# pressure_regulator_8ch.net
KiCad netlist of a schematic drawn in EAGLE
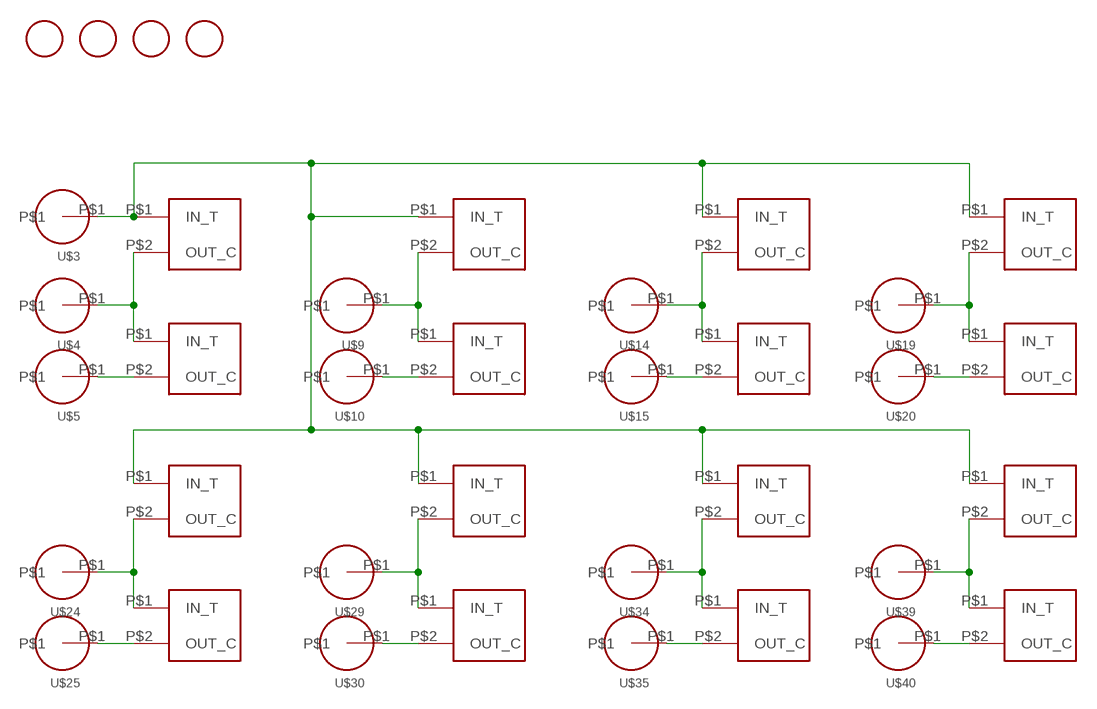
[diagram p0: schematic, sheet 1]

(export (version "E")
  (design (tool "Eeschema 10.0.6"))
  (components
    (comp (ref "U$1")
      (value "PARKER_PROP_VALVE")
      (footprint "eagle-import:PARKER_PROP_VALVE")
      (libsource (lib "eagle-import") (part "PARKER_PROP_VALVE"))
    )
    (comp (ref "U$2")
      (value "PARKER_PROP_VALVE")
      (footprint "eagle-import:PARKER_PROP_VALVE")
      (libsource (lib "eagle-import") (part "PARKER_PROP_VALVE"))
    )
    (comp (ref "U$3")
      (value "10-32_BARBED_CONNECTOR")
      (footprint "eagle-import:10-32_BARBED_CONNECTOR")
      (libsource (lib "eagle-import") (part "10-32_BARBED_CONNECTOR"))
    )
    (comp (ref "U$4")
      (value "10-32_BARBED_CONNECTOR")
      (footprint "eagle-import:10-32_BARBED_CONNECTOR")
      (libsource (lib "eagle-import") (part "10-32_BARBED_CONNECTOR"))
    )
    (comp (ref "U$5")
      (value "10-32_BARBED_CONNECTOR")
      (footprint "eagle-import:10-32_BARBED_CONNECTOR")
      (libsource (lib "eagle-import") (part "10-32_BARBED_CONNECTOR"))
    )
    (comp (ref "U$6")
      (value "PARKER_PROP_VALVE")
      (footprint "eagle-import:PARKER_PROP_VALVE")
      (libsource (lib "eagle-import") (part "PARKER_PROP_VALVE"))
    )
    (comp (ref "U$7")
      (value "PARKER_PROP_VALVE")
      (footprint "eagle-import:PARKER_PROP_VALVE")
      (libsource (lib "eagle-import") (part "PARKER_PROP_VALVE"))
    )
    (comp (ref "U$9")
      (value "10-32_BARBED_CONNECTOR")
      (footprint "eagle-import:10-32_BARBED_CONNECTOR")
      (libsource (lib "eagle-import") (part "10-32_BARBED_CONNECTOR"))
    )
    (comp (ref "U$10")
      (value "10-32_BARBED_CONNECTOR")
      (footprint "eagle-import:10-32_BARBED_CONNECTOR")
      (libsource (lib "eagle-import") (part "10-32_BARBED_CONNECTOR"))
    )
    (comp (ref "U$11")
      (value "PARKER_PROP_VALVE")
      (footprint "eagle-import:PARKER_PROP_VALVE")
      (libsource (lib "eagle-import") (part "PARKER_PROP_VALVE"))
    )
    (comp (ref "U$12")
      (value "PARKER_PROP_VALVE")
      (footprint "eagle-import:PARKER_PROP_VALVE")
      (libsource (lib "eagle-import") (part "PARKER_PROP_VALVE"))
    )
    (comp (ref "U$14")
      (value "10-32_BARBED_CONNECTOR")
      (footprint "eagle-import:10-32_BARBED_CONNECTOR")
      (libsource (lib "eagle-import") (part "10-32_BARBED_CONNECTOR"))
    )
    (comp (ref "U$15")
      (value "10-32_BARBED_CONNECTOR")
      (footprint "eagle-import:10-32_BARBED_CONNECTOR")
      (libsource (lib "eagle-import") (part "10-32_BARBED_CONNECTOR"))
    )
    (comp (ref "U$16")
      (value "PARKER_PROP_VALVE")
      (footprint "eagle-import:PARKER_PROP_VALVE")
      (libsource (lib "eagle-import") (part "PARKER_PROP_VALVE"))
    )
    (comp (ref "U$17")
      (value "PARKER_PROP_VALVE")
      (footprint "eagle-import:PARKER_PROP_VALVE")
      (libsource (lib "eagle-import") (part "PARKER_PROP_VALVE"))
    )
    (comp (ref "U$19")
      (value "10-32_BARBED_CONNECTOR")
      (footprint "eagle-import:10-32_BARBED_CONNECTOR")
      (libsource (lib "eagle-import") (part "10-32_BARBED_CONNECTOR"))
    )
    (comp (ref "U$20")
      (value "10-32_BARBED_CONNECTOR")
      (footprint "eagle-import:10-32_BARBED_CONNECTOR")
      (libsource (lib "eagle-import") (part "10-32_BARBED_CONNECTOR"))
    )
    (comp (ref "U$21")
      (value "PARKER_PROP_VALVE")
      (footprint "eagle-import:PARKER_PROP_VALVE")
      (libsource (lib "eagle-import") (part "PARKER_PROP_VALVE"))
    )
    (comp (ref "U$22")
      (value "PARKER_PROP_VALVE")
      (footprint "eagle-import:PARKER_PROP_VALVE")
      (libsource (lib "eagle-import") (part "PARKER_PROP_VALVE"))
    )
    (comp (ref "U$24")
      (value "10-32_BARBED_CONNECTOR")
      (footprint "eagle-import:10-32_BARBED_CONNECTOR")
      (libsource (lib "eagle-import") (part "10-32_BARBED_CONNECTOR"))
    )
    (comp (ref "U$25")
      (value "10-32_BARBED_CONNECTOR")
      (footprint "eagle-import:10-32_BARBED_CONNECTOR")
      (libsource (lib "eagle-import") (part "10-32_BARBED_CONNECTOR"))
    )
    (comp (ref "U$26")
      (value "PARKER_PROP_VALVE")
      (footprint "eagle-import:PARKER_PROP_VALVE")
      (libsource (lib "eagle-import") (part "PARKER_PROP_VALVE"))
    )
    (comp (ref "U$27")
      (value "PARKER_PROP_VALVE")
      (footprint "eagle-import:PARKER_PROP_VALVE")
      (libsource (lib "eagle-import") (part "PARKER_PROP_VALVE"))
    )
    (comp (ref "U$29")
      (value "10-32_BARBED_CONNECTOR")
      (footprint "eagle-import:10-32_BARBED_CONNECTOR")
      (libsource (lib "eagle-import") (part "10-32_BARBED_CONNECTOR"))
    )
    (comp (ref "U$30")
      (value "10-32_BARBED_CONNECTOR")
      (footprint "eagle-import:10-32_BARBED_CONNECTOR")
      (libsource (lib "eagle-import") (part "10-32_BARBED_CONNECTOR"))
    )
    (comp (ref "U$31")
      (value "PARKER_PROP_VALVE")
      (footprint "eagle-import:PARKER_PROP_VALVE")
      (libsource (lib "eagle-import") (part "PARKER_PROP_VALVE"))
    )
    (comp (ref "U$32")
      (value "PARKER_PROP_VALVE")
      (footprint "eagle-import:PARKER_PROP_VALVE")
      (libsource (lib "eagle-import") (part "PARKER_PROP_VALVE"))
    )
    (comp (ref "U$34")
      (value "10-32_BARBED_CONNECTOR")
      (footprint "eagle-import:10-32_BARBED_CONNECTOR")
      (libsource (lib "eagle-import") (part "10-32_BARBED_CONNECTOR"))
    )
    (comp (ref "U$35")
      (value "10-32_BARBED_CONNECTOR")
      (footprint "eagle-import:10-32_BARBED_CONNECTOR")
      (libsource (lib "eagle-import") (part "10-32_BARBED_CONNECTOR"))
    )
    (comp (ref "U$36")
      (value "PARKER_PROP_VALVE")
      (footprint "eagle-import:PARKER_PROP_VALVE")
      (libsource (lib "eagle-import") (part "PARKER_PROP_VALVE"))
    )
    (comp (ref "U$37")
      (value "PARKER_PROP_VALVE")
      (footprint "eagle-import:PARKER_PROP_VALVE")
      (libsource (lib "eagle-import") (part "PARKER_PROP_VALVE"))
    )
    (comp (ref "U$39")
      (value "10-32_BARBED_CONNECTOR")
      (footprint "eagle-import:10-32_BARBED_CONNECTOR")
      (libsource (lib "eagle-import") (part "10-32_BARBED_CONNECTOR"))
    )
    (comp (ref "U$40")
      (value "10-32_BARBED_CONNECTOR")
      (footprint "eagle-import:10-32_BARBED_CONNECTOR")
      (libsource (lib "eagle-import") (part "10-32_BARBED_CONNECTOR"))
    )
    (comp (ref "U$50")
      (value "M4")
      (footprint "eagle-import:M4")
      (libsource (lib "eagle-import") (part "M4"))
    )
    (comp (ref "U$51")
      (value "M4")
      (footprint "eagle-import:M4")
      (libsource (lib "eagle-import") (part "M4"))
    )
    (comp (ref "U$52")
      (value "M4")
      (footprint "eagle-import:M4")
      (libsource (lib "eagle-import") (part "M4"))
    )
    (comp (ref "U$53")
      (value "M4")
      (footprint "eagle-import:M4")
      (libsource (lib "eagle-import") (part "M4"))
    )
  )
  (nets
    (net (code "1") (name "Net-(U$1-IN_T)") (class "Default")
      (node (ref "U$1") (pin "P$1") (pinfunction "IN_T_P$1") (pintype "bidirectional"))
      (node (ref "U$11") (pin "P$1") (pinfunction "IN_T_P$1") (pintype "bidirectional"))
      (node (ref "U$16") (pin "P$1") (pinfunction "IN_T_P$1") (pintype "bidirectional"))
      (node (ref "U$21") (pin "P$1") (pinfunction "IN_T_P$1") (pintype "bidirectional"))
      (node (ref "U$26") (pin "P$1") (pinfunction "IN_T_P$1") (pintype "bidirectional"))
      (node (ref "U$3") (pin "P$1") (pinfunction "P$1_P$1") (pintype "bidirectional"))
      (node (ref "U$31") (pin "P$1") (pinfunction "IN_T_P$1") (pintype "bidirectional"))
      (node (ref "U$36") (pin "P$1") (pinfunction "IN_T_P$1") (pintype "bidirectional"))
      (node (ref "U$6") (pin "P$1") (pinfunction "IN_T_P$1") (pintype "bidirectional"))
    )
    (net (code "2") (name "Net-(U$1-OUT_C)") (class "Default")
      (node (ref "U$1") (pin "P$2") (pinfunction "OUT_C_P$2") (pintype "bidirectional"))
      (node (ref "U$2") (pin "P$1") (pinfunction "IN_T_P$1") (pintype "bidirectional"))
      (node (ref "U$4") (pin "P$1") (pinfunction "P$1_P$1") (pintype "bidirectional"))
    )
    (net (code "3") (name "Net-(U$2-OUT_C)") (class "Default")
      (node (ref "U$2") (pin "P$2") (pinfunction "OUT_C_P$2") (pintype "bidirectional"))
      (node (ref "U$5") (pin "P$1") (pinfunction "P$1_P$1") (pintype "bidirectional"))
    )
    (net (code "4") (name "Net-(U$6-OUT_C)") (class "Default")
      (node (ref "U$6") (pin "P$2") (pinfunction "OUT_C_P$2") (pintype "bidirectional"))
      (node (ref "U$7") (pin "P$1") (pinfunction "IN_T_P$1") (pintype "bidirectional"))
      (node (ref "U$9") (pin "P$1") (pinfunction "P$1_P$1") (pintype "bidirectional"))
    )
    (net (code "5") (name "Net-(U$7-OUT_C)") (class "Default")
      (node (ref "U$10") (pin "P$1") (pinfunction "P$1_P$1") (pintype "bidirectional"))
      (node (ref "U$7") (pin "P$2") (pinfunction "OUT_C_P$2") (pintype "bidirectional"))
    )
    (net (code "6") (name "Net-(U$11-OUT_C)") (class "Default")
      (node (ref "U$11") (pin "P$2") (pinfunction "OUT_C_P$2") (pintype "bidirectional"))
      (node (ref "U$12") (pin "P$1") (pinfunction "IN_T_P$1") (pintype "bidirectional"))
      (node (ref "U$14") (pin "P$1") (pinfunction "P$1_P$1") (pintype "bidirectional"))
    )
    (net (code "7") (name "Net-(U$12-OUT_C)") (class "Default")
      (node (ref "U$12") (pin "P$2") (pinfunction "OUT_C_P$2") (pintype "bidirectional"))
      (node (ref "U$15") (pin "P$1") (pinfunction "P$1_P$1") (pintype "bidirectional"))
    )
    (net (code "8") (name "Net-(U$16-OUT_C)") (class "Default")
      (node (ref "U$16") (pin "P$2") (pinfunction "OUT_C_P$2") (pintype "bidirectional"))
      (node (ref "U$17") (pin "P$1") (pinfunction "IN_T_P$1") (pintype "bidirectional"))
      (node (ref "U$19") (pin "P$1") (pinfunction "P$1_P$1") (pintype "bidirectional"))
    )
    (net (code "9") (name "Net-(U$17-OUT_C)") (class "Default")
      (node (ref "U$17") (pin "P$2") (pinfunction "OUT_C_P$2") (pintype "bidirectional"))
      (node (ref "U$20") (pin "P$1") (pinfunction "P$1_P$1") (pintype "bidirectional"))
    )
    (net (code "10") (name "Net-(U$21-OUT_C)") (class "Default")
      (node (ref "U$21") (pin "P$2") (pinfunction "OUT_C_P$2") (pintype "bidirectional"))
      (node (ref "U$22") (pin "P$1") (pinfunction "IN_T_P$1") (pintype "bidirectional"))
      (node (ref "U$24") (pin "P$1") (pinfunction "P$1_P$1") (pintype "bidirectional"))
    )
    (net (code "11") (name "Net-(U$22-OUT_C)") (class "Default")
      (node (ref "U$22") (pin "P$2") (pinfunction "OUT_C_P$2") (pintype "bidirectional"))
      (node (ref "U$25") (pin "P$1") (pinfunction "P$1_P$1") (pintype "bidirectional"))
    )
    (net (code "12") (name "Net-(U$26-OUT_C)") (class "Default")
      (node (ref "U$26") (pin "P$2") (pinfunction "OUT_C_P$2") (pintype "bidirectional"))
      (node (ref "U$27") (pin "P$1") (pinfunction "IN_T_P$1") (pintype "bidirectional"))
      (node (ref "U$29") (pin "P$1") (pinfunction "P$1_P$1") (pintype "bidirectional"))
    )
    (net (code "13") (name "Net-(U$27-OUT_C)") (class "Default")
      (node (ref "U$27") (pin "P$2") (pinfunction "OUT_C_P$2") (pintype "bidirectional"))
      (node (ref "U$30") (pin "P$1") (pinfunction "P$1_P$1") (pintype "bidirectional"))
    )
    (net (code "14") (name "Net-(U$31-OUT_C)") (class "Default")
      (node (ref "U$31") (pin "P$2") (pinfunction "OUT_C_P$2") (pintype "bidirectional"))
      (node (ref "U$32") (pin "P$1") (pinfunction "IN_T_P$1") (pintype "bidirectional"))
      (node (ref "U$34") (pin "P$1") (pinfunction "P$1_P$1") (pintype "bidirectional"))
    )
    (net (code "15") (name "Net-(U$32-OUT_C)") (class "Default")
      (node (ref "U$32") (pin "P$2") (pinfunction "OUT_C_P$2") (pintype "bidirectional"))
      (node (ref "U$35") (pin "P$1") (pinfunction "P$1_P$1") (pintype "bidirectional"))
    )
    (net (code "16") (name "Net-(U$36-OUT_C)") (class "Default")
      (node (ref "U$36") (pin "P$2") (pinfunction "OUT_C_P$2") (pintype "bidirectional"))
      (node (ref "U$37") (pin "P$1") (pinfunction "IN_T_P$1") (pintype "bidirectional"))
      (node (ref "U$39") (pin "P$1") (pinfunction "P$1_P$1") (pintype "bidirectional"))
    )
    (net (code "17") (name "Net-(U$37-OUT_C)") (class "Default")
      (node (ref "U$37") (pin "P$2") (pinfunction "OUT_C_P$2") (pintype "bidirectional"))
      (node (ref "U$40") (pin "P$1") (pinfunction "P$1_P$1") (pintype "bidirectional"))
    )
  )
)
